# LED.net
KiCad netlist of a schematic drawn in Altium Designer
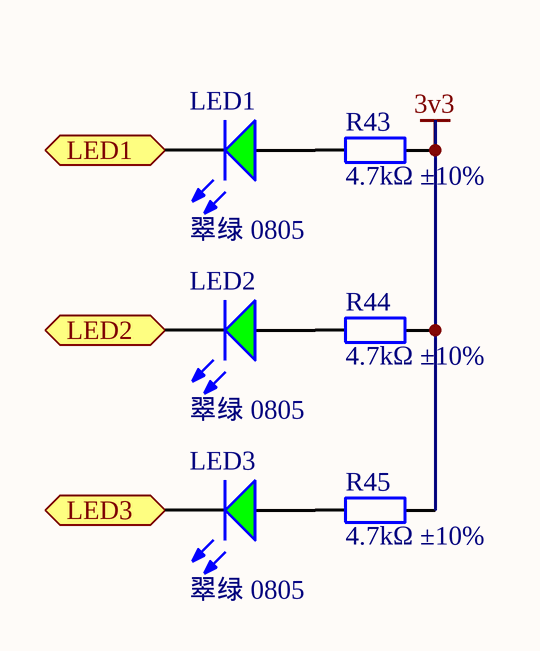
[diagram p0: LED.SchDoc]

(export (version "E")
  (design (tool "Eeschema 10.0.6"))
  (components
    (comp (ref "LED1")
      (value "翠绿 0805")
      (footprint "0805_LED_S1")
      (description "发光二极管")
      (libsource (lib "LED") (part "0805 翠绿"))
    )
    (comp (ref "LED2")
      (value "翠绿 0805")
      (footprint "0805_LED_S1")
      (description "发光二极管")
      (libsource (lib "LED") (part "0805 翠绿"))
    )
    (comp (ref "LED3")
      (value "翠绿 0805")
      (footprint "0805_LED_S1")
      (description "发光二极管")
      (libsource (lib "LED") (part "0805 翠绿"))
    )
    (comp (ref "R43")
      (value "4.7kΩ ±10%")
      (footprint "0603_R")
      (description "贴片电阻")
      (libsource (lib "RES") (part "0603 2.2Ω (2R20) 1%"))
    )
    (comp (ref "R44")
      (value "4.7kΩ ±10%")
      (footprint "0603_R")
      (description "贴片电阻")
      (libsource (lib "RES") (part "0603 2.2Ω (2R20) 1%"))
    )
    (comp (ref "R45")
      (value "4.7kΩ ±10%")
      (footprint "0603_R")
      (description "贴片电阻")
      (libsource (lib "RES") (part "0603 2.2Ω (2R20) 1%"))
    )
  )
  (nets
    (net (code "1") (name "/LED1") (class "Default")
      (node (ref "LED1") (pin "K") (pinfunction "K_K") (pintype "passive"))
    )
    (net (code "2") (name "/LED2") (class "Default")
      (node (ref "LED2") (pin "K") (pinfunction "K_K") (pintype "passive"))
    )
    (net (code "3") (name "/LED3") (class "Default")
      (node (ref "LED3") (pin "K") (pinfunction "K_K") (pintype "passive"))
    )
    (net (code "4") (name "3v3") (class "Default")
      (node (ref "R43") (pin "2") (pinfunction "2_2") (pintype "passive"))
      (node (ref "R44") (pin "2") (pinfunction "2_2") (pintype "passive"))
      (node (ref "R45") (pin "2") (pinfunction "2_2") (pintype "passive"))
    )
    (net (code "5") (name "Net-(LED1-PadA)") (class "Default")
      (node (ref "LED1") (pin "A") (pinfunction "A_A") (pintype "passive"))
      (node (ref "R43") (pin "1") (pinfunction "1_1") (pintype "passive"))
    )
    (net (code "6") (name "Net-(LED2-PadA)") (class "Default")
      (node (ref "LED2") (pin "A") (pinfunction "A_A") (pintype "passive"))
      (node (ref "R44") (pin "1") (pinfunction "1_1") (pintype "passive"))
    )
    (net (code "7") (name "Net-(LED3-PadA)") (class "Default")
      (node (ref "LED3") (pin "A") (pinfunction "A_A") (pintype "passive"))
      (node (ref "R45") (pin "1") (pinfunction "1_1") (pintype "passive"))
    )
  )
)
